# curtain.net
KiCad netlist of a schematic drawn in EAGLE
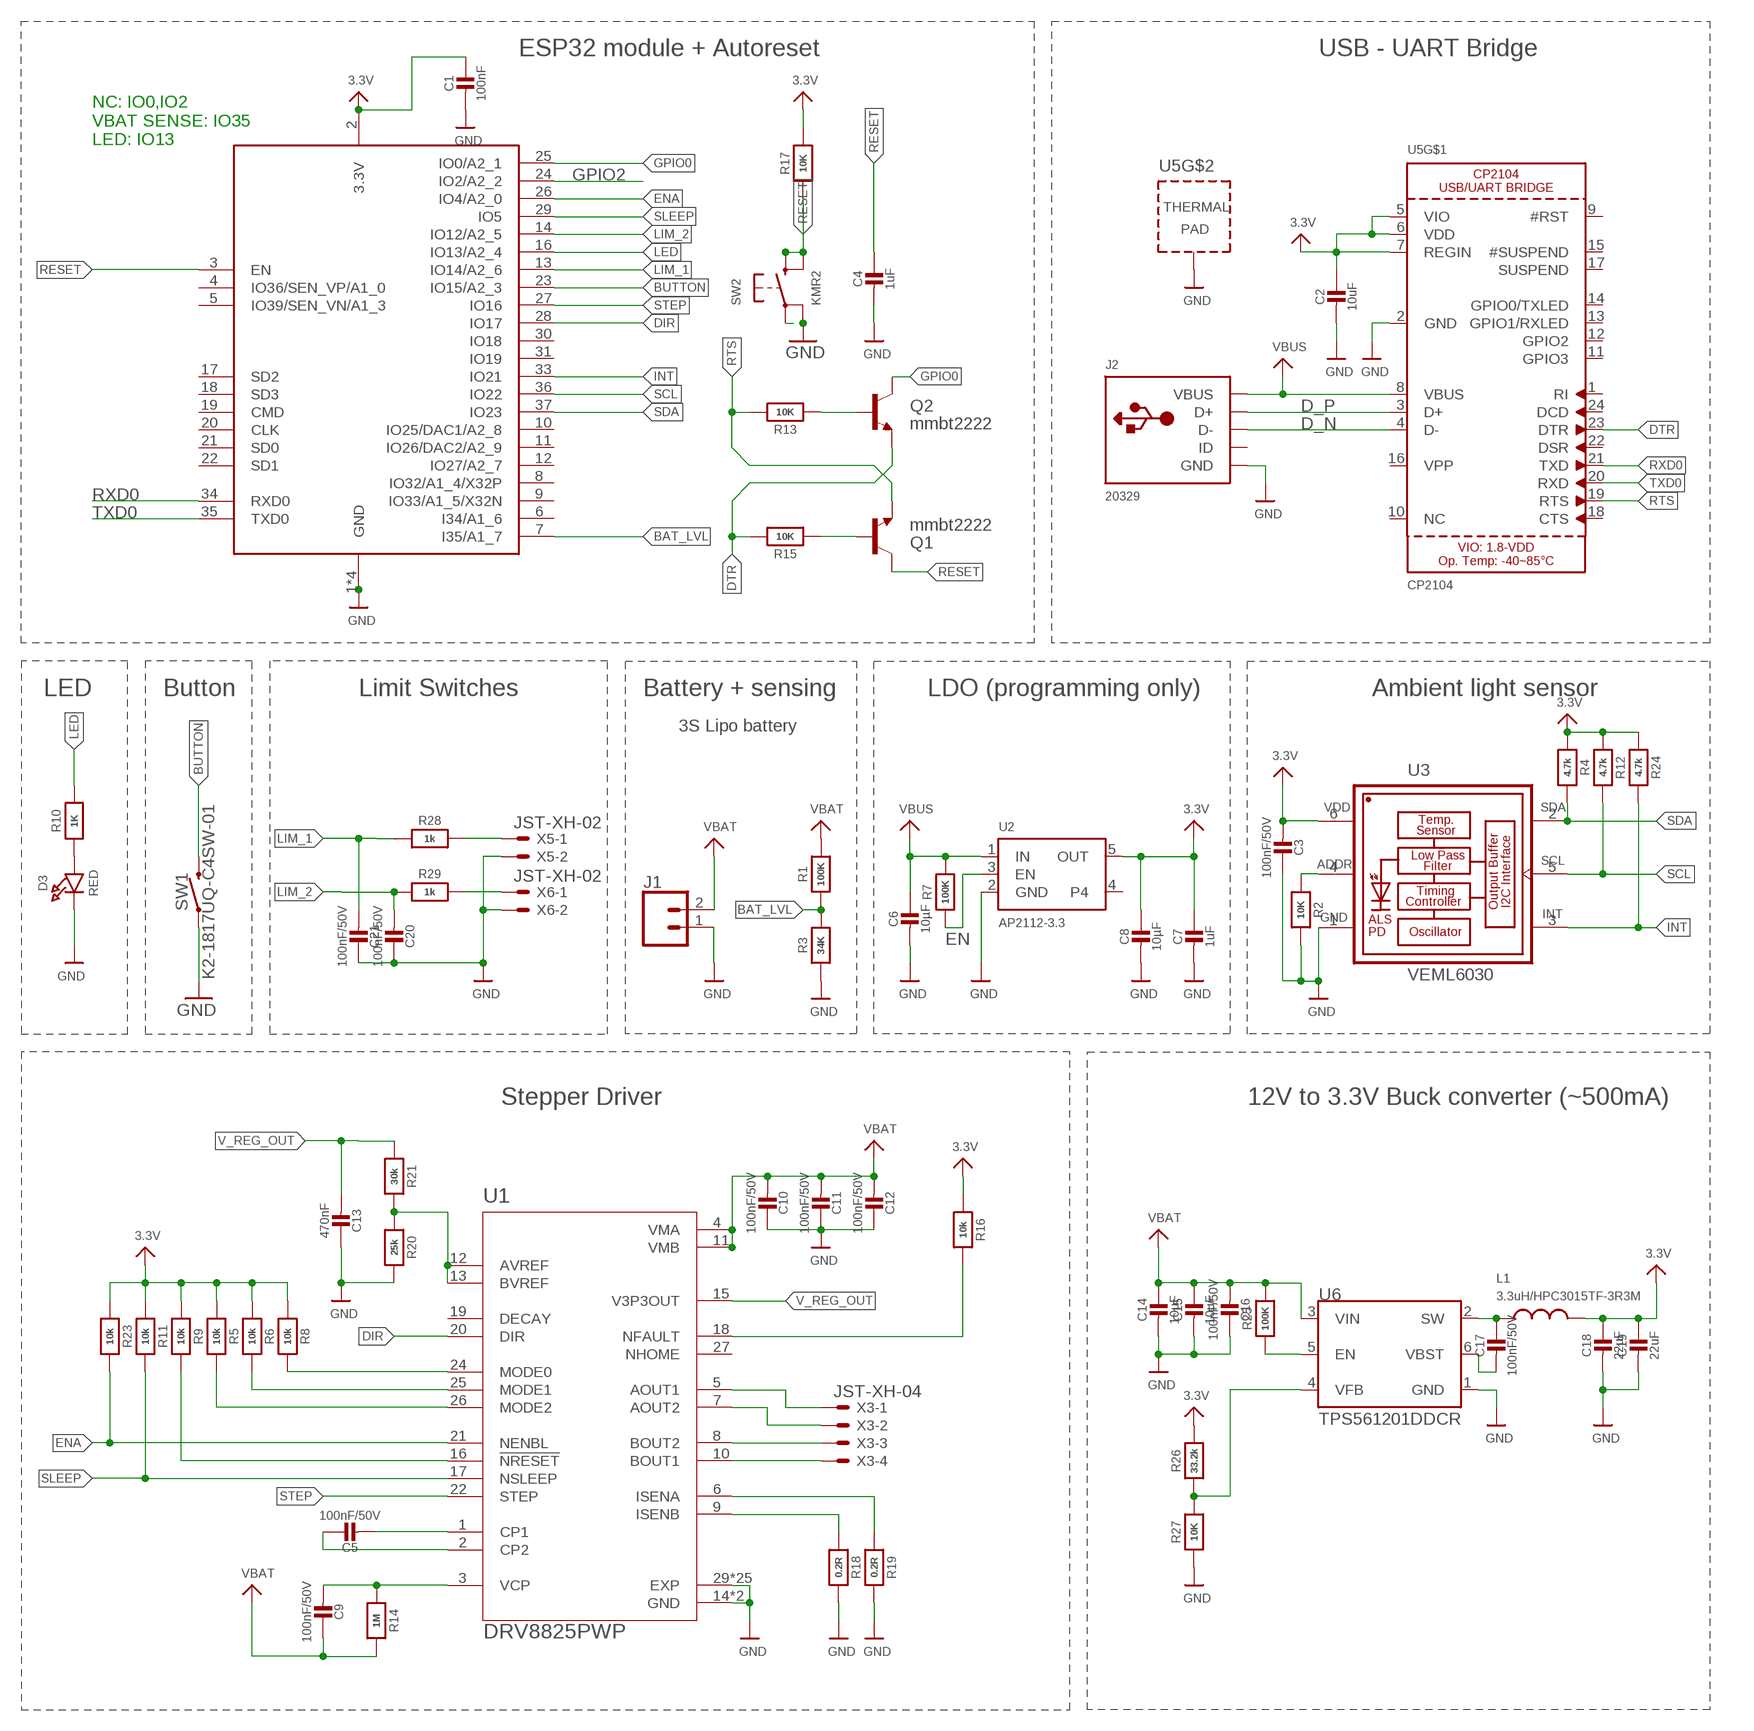
[diagram p0: schematic, sheet 1]

(export (version "E")
  (design (tool "Eeschema 10.0.6"))
  (components
    (comp (ref "C1")
      (value "100nF")
      (footprint "eagle-import:_0402")
      (libsource (lib "eagle-import") (part "CAP_CERAMIC_0402"))
    )
    (comp (ref "C2")
      (value "10uF")
      (footprint "eagle-import:_0402")
      (libsource (lib "eagle-import") (part "CAP_CERAMIC_0402"))
    )
    (comp (ref "C3")
      (value "100nF/50V")
      (footprint "eagle-import:_0402")
      (libsource (lib "eagle-import") (part "CAP_CERAMIC_0402"))
    )
    (comp (ref "C4")
      (value "1uF")
      (footprint "eagle-import:_0402")
      (libsource (lib "eagle-import") (part "CAP_CERAMIC_0402"))
    )
    (comp (ref "C5")
      (value "100nF/50V")
      (footprint "eagle-import:_0805")
      (libsource (lib "eagle-import") (part "CAP_CERAMIC_0805"))
    )
    (comp (ref "C6")
      (value "10µF")
      (footprint "eagle-import:_0402")
      (libsource (lib "eagle-import") (part "CAP_CERAMIC_0402"))
    )
    (comp (ref "C7")
      (value "1uF")
      (footprint "eagle-import:_0402")
      (libsource (lib "eagle-import") (part "CAP_CERAMIC_0402"))
    )
    (comp (ref "C8")
      (value "10µF")
      (footprint "eagle-import:_0402")
      (libsource (lib "eagle-import") (part "CAP_CERAMIC_0402"))
    )
    (comp (ref "C9")
      (value "100nF/50V")
      (footprint "eagle-import:_0805")
      (libsource (lib "eagle-import") (part "CAP_CERAMIC_0805"))
    )
    (comp (ref "C10")
      (value "100nF/50V")
      (footprint "eagle-import:_0805")
      (libsource (lib "eagle-import") (part "CAP_CERAMIC_0805"))
    )
    (comp (ref "C11")
      (value "100nF/50V")
      (footprint "eagle-import:_0805")
      (libsource (lib "eagle-import") (part "CAP_CERAMIC_0805"))
    )
    (comp (ref "C12")
      (value "100nF/50V")
      (footprint "eagle-import:_0805")
      (libsource (lib "eagle-import") (part "CAP_CERAMIC_0805"))
    )
    (comp (ref "C13")
      (value "470nF")
      (footprint "eagle-import:_0402")
      (libsource (lib "eagle-import") (part "CAP_CERAMIC_0402"))
    )
    (comp (ref "C14")
      (value "10µF")
      (footprint "eagle-import:_0402")
      (libsource (lib "eagle-import") (part "CAP_CERAMIC_0402"))
    )
    (comp (ref "C15")
      (value "10µF")
      (footprint "eagle-import:_0402")
      (libsource (lib "eagle-import") (part "CAP_CERAMIC_0402"))
    )
    (comp (ref "C16")
      (value "100nF/50V")
      (footprint "eagle-import:_0402")
      (libsource (lib "eagle-import") (part "CAP_CERAMIC_0402"))
    )
    (comp (ref "C17")
      (value "100nF/50V")
      (footprint "eagle-import:_0402")
      (libsource (lib "eagle-import") (part "CAP_CERAMIC_0402"))
    )
    (comp (ref "C18")
      (value "22uF")
      (footprint "eagle-import:_0402")
      (libsource (lib "eagle-import") (part "CAP_CERAMIC_0402"))
    )
    (comp (ref "C19")
      (value "22uF")
      (footprint "eagle-import:_0402")
      (libsource (lib "eagle-import") (part "CAP_CERAMIC_0402"))
    )
    (comp (ref "C20")
      (value "100nF/50V")
      (footprint "eagle-import:_0402")
      (libsource (lib "eagle-import") (part "CAP_CERAMIC_0402"))
    )
    (comp (ref "C21")
      (value "100nF/50V")
      (footprint "eagle-import:_0402")
      (libsource (lib "eagle-import") (part "CAP_CERAMIC_0402"))
    )
    (comp (ref "D3")
      (value "RED")
      (footprint "eagle-import:CHIPLED_0805_NOOUTLINE")
      (libsource (lib "eagle-import") (part "LED0805_NOOUTLINE"))
    )
    (comp (ref "J1")
      (value "CONN_023.5MM_LOCK")
      (footprint "eagle-import:SCREWTERMINAL-3.5MM-2_LOCK")
      (libsource (lib "eagle-import") (part "CONN_023.5MM_LOCK"))
    )
    (comp (ref "J2")
      (value "20329")
      (footprint "eagle-import:4UCONN_20329_V2")
      (libsource (lib "eagle-import") (part "USB_MICRO_20329_V2"))
    )
    (comp (ref "L1")
      (value "3.3uH/HPC3015TF-3R3M")
      (footprint "eagle-import:WPN4020H100MT")
      (libsource (lib "eagle-import") (part "WPN4020H100MT"))
    )
    (comp (ref "Q1")
      (value "mmbt2222")
      (footprint "eagle-import:SOT23-3")
      (libsource (lib "eagle-import") (part "TRANSISTOR_NPNSOT23-3"))
    )
    (comp (ref "Q2")
      (value "mmbt2222")
      (footprint "eagle-import:SOT23-3")
      (libsource (lib "eagle-import") (part "TRANSISTOR_NPNSOT23-3"))
    )
    (comp (ref "R1")
      (value "100K")
      (footprint "eagle-import:_0402")
      (libsource (lib "eagle-import") (part "RESISTOR_0402"))
    )
    (comp (ref "R2")
      (value "10K")
      (footprint "eagle-import:_0402")
      (libsource (lib "eagle-import") (part "RESISTOR_0402"))
    )
    (comp (ref "R3")
      (value "34K")
      (footprint "eagle-import:_0402")
      (libsource (lib "eagle-import") (part "RESISTOR_0402"))
    )
    (comp (ref "R4")
      (value "4.7k")
      (footprint "eagle-import:_0402")
      (libsource (lib "eagle-import") (part "RESISTOR_0402"))
    )
    (comp (ref "R5")
      (value "10k")
      (footprint "eagle-import:_0402")
      (libsource (lib "eagle-import") (part "RESISTOR_0402"))
    )
    (comp (ref "R6")
      (value "10k")
      (footprint "eagle-import:_0402")
      (libsource (lib "eagle-import") (part "RESISTOR_0402"))
    )
    (comp (ref "R7")
      (value "100K")
      (footprint "eagle-import:_0402")
      (libsource (lib "eagle-import") (part "RESISTOR_0402"))
    )
    (comp (ref "R8")
      (value "10k")
      (footprint "eagle-import:_0402")
      (libsource (lib "eagle-import") (part "RESISTOR_0402"))
    )
    (comp (ref "R9")
      (value "10k")
      (footprint "eagle-import:_0402")
      (libsource (lib "eagle-import") (part "RESISTOR_0402"))
    )
    (comp (ref "R10")
      (value "1K")
      (footprint "eagle-import:_0402")
      (libsource (lib "eagle-import") (part "RESISTOR_0402"))
    )
    (comp (ref "R11")
      (value "10k")
      (footprint "eagle-import:_0402")
      (libsource (lib "eagle-import") (part "RESISTOR_0402"))
    )
    (comp (ref "R12")
      (value "4.7k")
      (footprint "eagle-import:_0402")
      (libsource (lib "eagle-import") (part "RESISTOR_0402"))
    )
    (comp (ref "R13")
      (value "10K")
      (footprint "eagle-import:_0402")
      (libsource (lib "eagle-import") (part "RESISTOR_0402"))
    )
    (comp (ref "R14")
      (value "1M")
      (footprint "eagle-import:_0402")
      (libsource (lib "eagle-import") (part "RESISTOR_0402"))
    )
    (comp (ref "R15")
      (value "10K")
      (footprint "eagle-import:_0402")
      (libsource (lib "eagle-import") (part "RESISTOR_0402"))
    )
    (comp (ref "R16")
      (value "10k")
      (footprint "eagle-import:_0402")
      (libsource (lib "eagle-import") (part "RESISTOR_0402"))
    )
    (comp (ref "R17")
      (value "10K")
      (footprint "eagle-import:_0402")
      (libsource (lib "eagle-import") (part "RESISTOR_0402"))
    )
    (comp (ref "R18")
      (value "0.2R")
      (footprint "eagle-import:_1206")
      (libsource (lib "eagle-import") (part "RESISTOR_1206"))
    )
    (comp (ref "R19")
      (value "0.2R")
      (footprint "eagle-import:_1206")
      (libsource (lib "eagle-import") (part "RESISTOR_1206"))
    )
    (comp (ref "R20")
      (value "25k")
      (footprint "eagle-import:_0402")
      (libsource (lib "eagle-import") (part "RESISTOR_0402"))
    )
    (comp (ref "R21")
      (value "30k")
      (footprint "eagle-import:_0402")
      (libsource (lib "eagle-import") (part "RESISTOR_0402"))
    )
    (comp (ref "R23")
      (value "10k")
      (footprint "eagle-import:_0402")
      (libsource (lib "eagle-import") (part "RESISTOR_0402"))
    )
    (comp (ref "R24")
      (value "4.7k")
      (footprint "eagle-import:_0402")
      (libsource (lib "eagle-import") (part "RESISTOR_0402"))
    )
    (comp (ref "R25")
      (value "100K")
      (footprint "eagle-import:_0402")
      (libsource (lib "eagle-import") (part "RESISTOR_0402"))
    )
    (comp (ref "R26")
      (value "33.2k")
      (footprint "eagle-import:_0402")
      (libsource (lib "eagle-import") (part "RESISTOR_0402"))
    )
    (comp (ref "R27")
      (value "10K")
      (footprint "eagle-import:_0402")
      (libsource (lib "eagle-import") (part "RESISTOR_0402"))
    )
    (comp (ref "R28")
      (value "1k")
      (footprint "eagle-import:_0402")
      (libsource (lib "eagle-import") (part "RESISTOR_0402"))
    )
    (comp (ref "R29")
      (value "1k")
      (footprint "eagle-import:_0402")
      (libsource (lib "eagle-import") (part "RESISTOR_0402"))
    )
    (comp (ref "SW1")
      (value "K2-1817UQ-C4SW-01")
      (footprint "eagle-import:K2-1817UQ-C4SW-01")
      (libsource (lib "eagle-import") (part "K2-1817UQ-C4SW-01"))
    )
    (comp (ref "SW2")
      (value "KMR2")
      (footprint "eagle-import:BTN_KMR2_4.6X2.8")
      (libsource (lib "eagle-import") (part "SWITCH_TACT_SMT4.6X2.8"))
    )
    (comp (ref "U1")
      (value "DRV8825PWP")
      (footprint "eagle-import:SOP65P640X120-29N")
      (fields (field (name "MF") "Texas Instruments"))
      (libsource (lib "eagle-import") (part "DRV8825PWP"))
    )
    (comp (ref "U2")
      (value "AP2112-3.3")
      (footprint "eagle-import:SOT23-5")
      (libsource (lib "eagle-import") (part "VREG_SOT23-5"))
    )
    (comp (ref "U3")
      (value "VEML6030")
      (footprint "eagle-import:VISHAY_VEML6030_2X2X0.87")
      (fields (field (name "MF") "Vishay"))
      (libsource (lib "eagle-import") (part "VEML6030"))
    )
    (comp (ref "U4")
      (value "ESP32_WROOM32_SKINNY")
      (footprint "eagle-import:WROOM32_SKINNY")
      (libsource (lib "eagle-import") (part "ESP32_WROOM32_SKINNY"))
    )
    (comp (ref "U5")
      (value "CP2104")
      (footprint "eagle-import:QFN24_4MM_SMSC")
      (libsource (lib "eagle-import") (part "CP2104"))
    )
    (comp (ref "U6")
      (value "TPS561201DDCR")
      (footprint "eagle-import:SOT95P280X110-6N")
      (fields (field (name "MF") "Texas Instruments"))
      (libsource (lib "eagle-import") (part "TPS561201DDCR"))
    )
    (comp (ref "X3")
      (value "JST-XH-04")
      (footprint "eagle-import:JST-XH-04-PACKAGE-ROUND-PAD")
      (libsource (lib "eagle-import") (part "JST-XH-04-PIN-ROUND-PAD"))
    )
    (comp (ref "X5")
      (value "JST-XH-02")
      (footprint "eagle-import:JST-XH-02-PACKAGE-ROUND-PAD")
      (libsource (lib "eagle-import") (part "JST-XH-02-PIN-ROUND-PAD"))
    )
    (comp (ref "X6")
      (value "JST-XH-02")
      (footprint "eagle-import:JST-XH-02-PACKAGE-ROUND-PAD")
      (libsource (lib "eagle-import") (part "JST-XH-02-PIN-ROUND-PAD"))
    )
  )
  (nets
    (net (code "1") (name "/D_N") (class "Default")
      (node (ref "J2") (pin "D-") (pinfunction "D-_D-") (pintype "bidirectional"))
      (node (ref "U5") (pin "4") (pinfunction "D-_4") (pintype "bidirectional"))
    )
    (net (code "2") (name "/D_P") (class "Default")
      (node (ref "J2") (pin "D+") (pinfunction "D+_D+") (pintype "bidirectional"))
      (node (ref "U5") (pin "3") (pinfunction "D+_3") (pintype "bidirectional"))
    )
    (net (code "3") (name "/EN") (class "Default")
      (node (ref "R7") (pin "1") (pinfunction "1_1") (pintype "passive"))
      (node (ref "U2") (pin "3") (pinfunction "EN_3") (pintype "input"))
    )
    (net (code "4") (name "/GPIO2") (class "Default")
      (node (ref "U4") (pin "24") (pinfunction "IO2/A2_2_24") (pintype "bidirectional"))
    )
    (net (code "5") (name "3.3V") (class "Default")
      (node (ref "C1") (pin "1") (pinfunction "1_1") (pintype "passive"))
      (node (ref "C18") (pin "1") (pinfunction "1_1") (pintype "passive"))
      (node (ref "C19") (pin "1") (pinfunction "1_1") (pintype "passive"))
      (node (ref "C2") (pin "1") (pinfunction "1_1") (pintype "passive"))
      (node (ref "C3") (pin "2") (pinfunction "2_2") (pintype "passive"))
      (node (ref "C7") (pin "1") (pinfunction "1_1") (pintype "passive"))
      (node (ref "C8") (pin "1") (pinfunction "1_1") (pintype "passive"))
      (node (ref "L1") (pin "2") (pinfunction "2_2") (pintype "passive"))
      (node (ref "R11") (pin "1") (pinfunction "1_1") (pintype "passive"))
      (node (ref "R12") (pin "1") (pinfunction "1_1") (pintype "passive"))
      (node (ref "R16") (pin "1") (pinfunction "1_1") (pintype "passive"))
      (node (ref "R17") (pin "2") (pinfunction "2_2") (pintype "passive"))
      (node (ref "R23") (pin "1") (pinfunction "1_1") (pintype "passive"))
      (node (ref "R24") (pin "1") (pinfunction "1_1") (pintype "passive"))
      (node (ref "R26") (pin "1") (pinfunction "1_1") (pintype "passive"))
      (node (ref "R4") (pin "1") (pinfunction "1_1") (pintype "passive"))
      (node (ref "R5") (pin "1") (pinfunction "1_1") (pintype "passive"))
      (node (ref "R6") (pin "1") (pinfunction "1_1") (pintype "passive"))
      (node (ref "R8") (pin "1") (pinfunction "1_1") (pintype "passive"))
      (node (ref "R9") (pin "1") (pinfunction "1_1") (pintype "passive"))
      (node (ref "U2") (pin "5") (pinfunction "OUT_5") (pintype "power_in"))
      (node (ref "U3") (pin "6") (pinfunction "VDD_6") (pintype "power_in"))
      (node (ref "U4") (pin "2") (pinfunction "3.3V_2") (pintype "passive"))
      (node (ref "U5") (pin "5") (pinfunction "VIO_5") (pintype "power_in"))
      (node (ref "U5") (pin "6") (pinfunction "VDD_6") (pintype "power_in"))
      (node (ref "U5") (pin "7") (pinfunction "REGIN_7") (pintype "power_in"))
    )
    (net (code "6") (name "BAT_LVL") (class "Default")
      (node (ref "R1") (pin "1") (pinfunction "1_1") (pintype "passive"))
      (node (ref "R3") (pin "2") (pinfunction "2_2") (pintype "passive"))
      (node (ref "U4") (pin "7") (pinfunction "I35/A1_7_7") (pintype "bidirectional"))
    )
    (net (code "7") (name "BUTTON") (class "Default")
      (node (ref "SW1") (pin "P$2") (pinfunction "2_P$2") (pintype "passive"))
      (node (ref "U4") (pin "23") (pinfunction "IO15/A2_3_23") (pintype "bidirectional"))
    )
    (net (code "8") (name "DIR") (class "Default")
      (node (ref "U1") (pin "20") (pinfunction "DIR_20") (pintype "input"))
      (node (ref "U4") (pin "28") (pinfunction "IO17_28") (pintype "bidirectional"))
    )
    (net (code "9") (name "DTR") (class "Default")
      (node (ref "Q2") (pin "2") (pinfunction "E_2") (pintype "passive"))
      (node (ref "R15") (pin "2") (pinfunction "2_2") (pintype "passive"))
      (node (ref "U5") (pin "23") (pinfunction "DTR_23") (pintype "output"))
    )
    (net (code "10") (name "ENA") (class "Default")
      (node (ref "R23") (pin "2") (pinfunction "2_2") (pintype "passive"))
      (node (ref "U1") (pin "21") (pinfunction "NENBL_21") (pintype "input"))
      (node (ref "U4") (pin "26") (pinfunction "IO4/A2_0_26") (pintype "bidirectional"))
    )
    (net (code "11") (name "GND") (class "Default")
      (node (ref "C1") (pin "2") (pinfunction "2_2") (pintype "passive"))
      (node (ref "C10") (pin "1") (pinfunction "1_1") (pintype "passive"))
      (node (ref "C11") (pin "1") (pinfunction "1_1") (pintype "passive"))
      (node (ref "C12") (pin "1") (pinfunction "1_1") (pintype "passive"))
      (node (ref "C13") (pin "1") (pinfunction "1_1") (pintype "passive"))
      (node (ref "C14") (pin "2") (pinfunction "2_2") (pintype "passive"))
      (node (ref "C15") (pin "2") (pinfunction "2_2") (pintype "passive"))
      (node (ref "C16") (pin "1") (pinfunction "1_1") (pintype "passive"))
      (node (ref "C18") (pin "2") (pinfunction "2_2") (pintype "passive"))
      (node (ref "C19") (pin "2") (pinfunction "2_2") (pintype "passive"))
      (node (ref "C2") (pin "2") (pinfunction "2_2") (pintype "passive"))
      (node (ref "C20") (pin "1") (pinfunction "1_1") (pintype "passive"))
      (node (ref "C21") (pin "1") (pinfunction "1_1") (pintype "passive"))
      (node (ref "C3") (pin "1") (pinfunction "1_1") (pintype "passive"))
      (node (ref "C4") (pin "2") (pinfunction "2_2") (pintype "passive"))
      (node (ref "C6") (pin "2") (pinfunction "2_2") (pintype "passive"))
      (node (ref "C7") (pin "2") (pinfunction "2_2") (pintype "passive"))
      (node (ref "C8") (pin "2") (pinfunction "2_2") (pintype "passive"))
      (node (ref "D3") (pin "C") (pinfunction "C_C") (pintype "passive"))
      (node (ref "J1") (pin "1") (pinfunction "1_1") (pintype "passive"))
      (node (ref "J2") (pin "BASE@1") (pinfunction "GND_BASE@1") (pintype "power_in"))
      (node (ref "J2") (pin "BASE@2") (pinfunction "GND_BASE@2") (pintype "power_in"))
      (node (ref "J2") (pin "GND") (pinfunction "GND_GND") (pintype "power_in"))
      (node (ref "J2") (pin "SPRT@1") (pinfunction "GND_SPRT@1") (pintype "power_in"))
      (node (ref "J2") (pin "SPRT@2") (pinfunction "GND_SPRT@2") (pintype "power_in"))
      (node (ref "J2") (pin "SPRT@3") (pinfunction "GND_SPRT@3") (pintype "power_in"))
      (node (ref "J2") (pin "SPRT@4") (pinfunction "GND_SPRT@4") (pintype "power_in"))
      (node (ref "R18") (pin "2") (pinfunction "2_2") (pintype "passive"))
      (node (ref "R19") (pin "2") (pinfunction "2_2") (pintype "passive"))
      (node (ref "R2") (pin "2") (pinfunction "2_2") (pintype "passive"))
      (node (ref "R20") (pin "2") (pinfunction "2_2") (pintype "passive"))
      (node (ref "R27") (pin "1") (pinfunction "1_1") (pintype "passive"))
      (node (ref "R3") (pin "1") (pinfunction "1_1") (pintype "passive"))
      (node (ref "SW1") (pin "P$1") (pinfunction "1_P$1") (pintype "passive"))
      (node (ref "SW2") (pin "A'") (pinfunction "P1_A'") (pintype "passive"))
      (node (ref "U1") (pin "14") (pinfunction "GND_14") (pintype "power_in"))
      (node (ref "U1") (pin "28") (pinfunction "GND_28") (pintype "power_in"))
      (node (ref "U1") (pin "29") (pinfunction "EXP_29") (pintype "power_in"))
      (node (ref "U1") (pin "P1") (pinfunction "EXP_P1") (pintype "power_in"))
      (node (ref "U1") (pin "P10") (pinfunction "EXP_P10") (pintype "power_in"))
      (node (ref "U1") (pin "P11") (pinfunction "EXP_P11") (pintype "power_in"))
      (node (ref "U1") (pin "P12") (pinfunction "EXP_P12") (pintype "power_in"))
      (node (ref "U1") (pin "P13") (pinfunction "EXP_P13") (pintype "power_in"))
      (node (ref "U1") (pin "P14") (pinfunction "EXP_P14") (pintype "power_in"))
      (node (ref "U1") (pin "P15") (pinfunction "EXP_P15") (pintype "power_in"))
      (node (ref "U1") (pin "P16") (pinfunction "EXP_P16") (pintype "power_in"))
      (node (ref "U1") (pin "P17") (pinfunction "EXP_P17") (pintype "power_in"))
      (node (ref "U1") (pin "P18") (pinfunction "EXP_P18") (pintype "power_in"))
      (node (ref "U1") (pin "P19") (pinfunction "EXP_P19") (pintype "power_in"))
      (node (ref "U1") (pin "P2") (pinfunction "EXP_P2") (pintype "power_in"))
      (node (ref "U1") (pin "P20") (pinfunction "EXP_P20") (pintype "power_in"))
      (node (ref "U1") (pin "P21") (pinfunction "EXP_P21") (pintype "power_in"))
      (node (ref "U1") (pin "P22") (pinfunction "EXP_P22") (pintype "power_in"))
      (node (ref "U1") (pin "P23") (pinfunction "EXP_P23") (pintype "power_in"))
      (node (ref "U1") (pin "P24") (pinfunction "EXP_P24") (pintype "power_in"))
      (node (ref "U1") (pin "P3") (pinfunction "EXP_P3") (pintype "power_in"))
      (node (ref "U1") (pin "P4") (pinfunction "EXP_P4") (pintype "power_in"))
      (node (ref "U1") (pin "P5") (pinfunction "EXP_P5") (pintype "power_in"))
      (node (ref "U1") (pin "P6") (pinfunction "EXP_P6") (pintype "power_in"))
      (node (ref "U1") (pin "P7") (pinfunction "EXP_P7") (pintype "power_in"))
      (node (ref "U1") (pin "P8") (pinfunction "EXP_P8") (pintype "power_in"))
      (node (ref "U1") (pin "P9") (pinfunction "EXP_P9") (pintype "power_in"))
      (node (ref "U2") (pin "2") (pinfunction "GND_2") (pintype "power_in"))
      (node (ref "U3") (pin "1") (pinfunction "GND_1") (pintype "power_in"))
      (node (ref "U4") (pin "1") (pinfunction "GND_1") (pintype "passive"))
      (node (ref "U4") (pin "15") (pinfunction "GND_15") (pintype "passive"))
      (node (ref "U4") (pin "38") (pinfunction "GND_38") (pintype "passive"))
      (node (ref "U4") (pin "P$1") (pinfunction "GND_P$1") (pintype "passive"))
      (node (ref "U5") (pin "2") (pinfunction "GND_2") (pintype "power_in"))
      (node (ref "U5") (pin "THERM") (pinfunction "TP_THERM") (pintype "power_in"))
      (node (ref "U6") (pin "1") (pinfunction "GND_1") (pintype "power_in"))
      (node (ref "X5") (pin "2") (pinfunction "S_2") (pintype "passive"))
      (node (ref "X6") (pin "2") (pinfunction "S_2") (pintype "passive"))
    )
    (net (code "12") (name "GPIO0") (class "Default")
      (node (ref "Q2") (pin "3") (pinfunction "C_3") (pintype "passive"))
      (node (ref "U4") (pin "25") (pinfunction "IO0/A2_1_25") (pintype "bidirectional"))
    )
    (net (code "13") (name "INT") (class "Default")
      (node (ref "R24") (pin "2") (pinfunction "2_2") (pintype "passive"))
      (node (ref "U3") (pin "3") (pinfunction "INT_3") (pintype "output"))
      (node (ref "U4") (pin "33") (pinfunction "IO21_33") (pintype "bidirectional"))
    )
    (net (code "14") (name "LED") (class "Default")
      (node (ref "R10") (pin "1") (pinfunction "1_1") (pintype "passive"))
      (node (ref "U4") (pin "16") (pinfunction "IO13/A2_4_16") (pintype "bidirectional"))
    )
    (net (code "15") (name "LIM_1") (class "Default")
      (node (ref "C21") (pin "2") (pinfunction "2_2") (pintype "passive"))
      (node (ref "R28") (pin "1") (pinfunction "1_1") (pintype "passive"))
      (node (ref "U4") (pin "13") (pinfunction "IO14/A2_6_13") (pintype "bidirectional"))
    )
    (net (code "16") (name "LIM_2") (class "Default")
      (node (ref "C20") (pin "2") (pinfunction "2_2") (pintype "passive"))
      (node (ref "R29") (pin "1") (pinfunction "1_1") (pintype "passive"))
      (node (ref "U4") (pin "14") (pinfunction "IO12/A2_5_14") (pintype "bidirectional"))
    )
    (net (code "17") (name "Net-(D3-PadA)") (class "Default")
      (node (ref "D3") (pin "A") (pinfunction "A_A") (pintype "passive"))
      (node (ref "R10") (pin "2") (pinfunction "2_2") (pintype "passive"))
    )
    (net (code "18") (name "Net-(Q1-B)") (class "Default")
      (node (ref "Q1") (pin "1") (pinfunction "B_1") (pintype "passive"))
      (node (ref "R15") (pin "1") (pinfunction "1_1") (pintype "passive"))
    )
    (net (code "19") (name "Net-(Q2-B)") (class "Default")
      (node (ref "Q2") (pin "1") (pinfunction "B_1") (pintype "passive"))
      (node (ref "R13") (pin "1") (pinfunction "1_1") (pintype "passive"))
    )
    (net (code "20") (name "Net-(U1-AOUT1)") (class "Default")
      (node (ref "U1") (pin "5") (pinfunction "AOUT1_5") (pintype "output"))
      (node (ref "X3") (pin "1") (pinfunction "S_1") (pintype "passive"))
    )
    (net (code "21") (name "Net-(U1-AOUT2)") (class "Default")
      (node (ref "U1") (pin "7") (pinfunction "AOUT2_7") (pintype "output"))
      (node (ref "X3") (pin "2") (pinfunction "S_2") (pintype "passive"))
    )
    (net (code "22") (name "Net-(U1-AVREF)") (class "Default")
      (node (ref "R20") (pin "1") (pinfunction "1_1") (pintype "passive"))
      (node (ref "R21") (pin "2") (pinfunction "2_2") (pintype "passive"))
      (node (ref "U1") (pin "12") (pinfunction "AVREF_12") (pintype "input"))
      (node (ref "U1") (pin "13") (pinfunction "BVREF_13") (pintype "input"))
    )
    (net (code "23") (name "Net-(U1-BOUT1)") (class "Default")
      (node (ref "U1") (pin "10") (pinfunction "BOUT1_10") (pintype "output"))
      (node (ref "X3") (pin "4") (pinfunction "S_4") (pintype "passive"))
    )
    (net (code "24") (name "Net-(U1-BOUT2)") (class "Default")
      (node (ref "U1") (pin "8") (pinfunction "BOUT2_8") (pintype "output"))
      (node (ref "X3") (pin "3") (pinfunction "S_3") (pintype "passive"))
    )
    (net (code "25") (name "Net-(U1-CP1)") (class "Default")
      (node (ref "C5") (pin "2") (pinfunction "2_2") (pintype "passive"))
      (node (ref "U1") (pin "1") (pinfunction "CP1_1") (pintype "bidirectional"))
    )
    (net (code "26") (name "Net-(U1-CP2)") (class "Default")
      (node (ref "C5") (pin "1") (pinfunction "1_1") (pintype "passive"))
      (node (ref "U1") (pin "2") (pinfunction "CP2_2") (pintype "bidirectional"))
    )
    (net (code "27") (name "Net-(U1-ISENA)") (class "Default")
      (node (ref "R19") (pin "1") (pinfunction "1_1") (pintype "passive"))
      (node (ref "U1") (pin "6") (pinfunction "ISENA_6") (pintype "bidirectional"))
    )
    (net (code "28") (name "Net-(U1-ISENB)") (class "Default")
      (node (ref "R18") (pin "1") (pinfunction "1_1") (pintype "passive"))
      (node (ref "U1") (pin "9") (pinfunction "ISENB_9") (pintype "bidirectional"))
    )
    (net (code "29") (name "Net-(U1-MODE0)") (class "Default")
      (node (ref "R8") (pin "2") (pinfunction "2_2") (pintype "passive"))
      (node (ref "U1") (pin "24") (pinfunction "MODE0_24") (pintype "input"))
    )
    (net (code "30") (name "Net-(U1-MODE1)") (class "Default")
      (node (ref "R6") (pin "2") (pinfunction "2_2") (pintype "passive"))
      (node (ref "U1") (pin "25") (pinfunction "MODE1_25") (pintype "input"))
    )
    (net (code "31") (name "Net-(U1-MODE2)") (class "Default")
      (node (ref "R5") (pin "2") (pinfunction "2_2") (pintype "passive"))
      (node (ref "U1") (pin "26") (pinfunction "MODE2_26") (pintype "input"))
    )
    (net (code "32") (name "Net-(U1-NFAULT)") (class "Default")
      (node (ref "R16") (pin "2") (pinfunction "2_2") (pintype "passive"))
      (node (ref "U1") (pin "18") (pinfunction "NFAULT_18") (pintype "output"))
    )
    (net (code "33") (name "Net-(U1-VCP)") (class "Default")
      (node (ref "C9") (pin "2") (pinfunction "2_2") (pintype "passive"))
      (node (ref "R14") (pin "1") (pinfunction "1_1") (pintype "passive"))
      (node (ref "U1") (pin "3") (pinfunction "VCP_3") (pintype "bidirectional"))
    )
    (net (code "34") (name "Net-(U1-~{NRESET})") (class "Default")
      (node (ref "R9") (pin "2") (pinfunction "2_2") (pintype "passive"))
      (node (ref "U1") (pin "16") (pinfunction "~{NRESET}_16") (pintype "input"))
    )
    (net (code "35") (name "Net-(U3-ADDR)") (class "Default")
      (node (ref "R2") (pin "1") (pinfunction "1_1") (pintype "passive"))
      (node (ref "U3") (pin "4") (pinfunction "ADDR_4") (pintype "bidirectional"))
    )
    (net (code "36") (name "Net-(U6-EN)") (class "Default")
      (node (ref "R25") (pin "1") (pinfunction "1_1") (pintype "passive"))
      (node (ref "U6") (pin "5") (pinfunction "EN_5") (pintype "input"))
    )
    (net (code "37") (name "Net-(U6-SW)") (class "Default")
      (node (ref "C17") (pin "1") (pinfunction "1_1") (pintype "passive"))
      (node (ref "L1") (pin "1") (pinfunction "1_1") (pintype "passive"))
      (node (ref "U6") (pin "2") (pinfunction "SW_2") (pintype "output"))
    )
    (net (code "38") (name "Net-(U6-VBST)") (class "Default")
      (node (ref "C17") (pin "2") (pinfunction "2_2") (pintype "passive"))
      (node (ref "U6") (pin "6") (pinfunction "VBST_6") (pintype "passive"))
    )
    (net (code "39") (name "Net-(U6-VFB)") (class "Default")
      (node (ref "R26") (pin "2") (pinfunction "2_2") (pintype "passive"))
      (node (ref "R27") (pin "2") (pinfunction "2_2") (pintype "passive"))
      (node (ref "U6") (pin "4") (pinfunction "VFB_4") (pintype "input"))
    )
    (net (code "40") (name "Net-(X5A-S)") (class "Default")
      (node (ref "R28") (pin "2") (pinfunction "2_2") (pintype "passive"))
      (node (ref "X5") (pin "1") (pinfunction "S_1") (pintype "passive"))
    )
    (net (code "41") (name "Net-(X6A-S)") (class "Default")
      (node (ref "R29") (pin "2") (pinfunction "2_2") (pintype "passive"))
      (node (ref "X6") (pin "1") (pinfunction "S_1") (pintype "passive"))
    )
    (net (code "42") (name "RESET") (class "Default")
      (node (ref "C4") (pin "1") (pinfunction "1_1") (pintype "passive"))
      (node (ref "Q1") (pin "3") (pinfunction "C_3") (pintype "passive"))
      (node (ref "R17") (pin "1") (pinfunction "1_1") (pintype "passive"))
      (node (ref "SW2") (pin "B") (pinfunction "S_B") (pintype "passive"))
      (node (ref "SW2") (pin "B'") (pinfunction "S1_B'") (pintype "passive"))
      (node (ref "U4") (pin "3") (pinfunction "EN_3") (pintype "input"))
    )
    (net (code "43") (name "RTS") (class "Default")
      (node (ref "Q1") (pin "2") (pinfunction "E_2") (pintype "passive"))
      (node (ref "R13") (pin "2") (pinfunction "2_2") (pintype "passive"))
      (node (ref "U5") (pin "19") (pinfunction "RTS_19") (pintype "output"))
    )
    (net (code "44") (name "RXD0") (class "Default")
      (node (ref "U4") (pin "34") (pinfunction "RXD0_34") (pintype "input"))
      (node (ref "U5") (pin "21") (pinfunction "TXD_21") (pintype "output"))
    )
    (net (code "45") (name "SCL") (class "Default")
      (node (ref "R12") (pin "2") (pinfunction "2_2") (pintype "passive"))
      (node (ref "U3") (pin "5") (pinfunction "SCL_5") (pintype "input"))
      (node (ref "U4") (pin "36") (pinfunction "IO22_36") (pintype "bidirectional"))
    )
    (net (code "46") (name "SDA") (class "Default")
      (node (ref "R4") (pin "2") (pinfunction "2_2") (pintype "passive"))
      (node (ref "U3") (pin "2") (pinfunction "SDA_2") (pintype "bidirectional"))
      (node (ref "U4") (pin "37") (pinfunction "IO23_37") (pintype "bidirectional"))
    )
    (net (code "47") (name "SLEEP") (class "Default")
      (node (ref "R11") (pin "2") (pinfunction "2_2") (pintype "passive"))
      (node (ref "U1") (pin "17") (pinfunction "NSLEEP_17") (pintype "input"))
      (node (ref "U4") (pin "29") (pinfunction "IO5_29") (pintype "bidirectional"))
    )
    (net (code "48") (name "STEP") (class "Default")
      (node (ref "U1") (pin "22") (pinfunction "STEP_22") (pintype "input"))
      (node (ref "U4") (pin "27") (pinfunction "IO16_27") (pintype "bidirectional"))
    )
    (net (code "49") (name "TXD0") (class "Default")
      (node (ref "U4") (pin "35") (pinfunction "TXD0_35") (pintype "output"))
      (node (ref "U5") (pin "20") (pinfunction "RXD_20") (pintype "input"))
    )
    (net (code "50") (name "VBAT") (class "Default")
      (node (ref "C10") (pin "2") (pinfunction "2_2") (pintype "passive"))
      (node (ref "C11") (pin "2") (pinfunction "2_2") (pintype "passive"))
      (node (ref "C12") (pin "2") (pinfunction "2_2") (pintype "passive"))
      (node (ref "C14") (pin "1") (pinfunction "1_1") (pintype "passive"))
      (node (ref "C15") (pin "1") (pinfunction "1_1") (pintype "passive"))
      (node (ref "C16") (pin "2") (pinfunction "2_2") (pintype "passive"))
      (node (ref "C9") (pin "1") (pinfunction "1_1") (pintype "passive"))
      (node (ref "J1") (pin "2") (pinfunction "2_2") (pintype "passive"))
      (node (ref "R1") (pin "2") (pinfunction "2_2") (pintype "passive"))
      (node (ref "R14") (pin "2") (pinfunction "2_2") (pintype "passive"))
      (node (ref "R25") (pin "2") (pinfunction "2_2") (pintype "passive"))
      (node (ref "U1") (pin "11") (pinfunction "VMB_11") (pintype "power_in"))
      (node (ref "U1") (pin "4") (pinfunction "VMA_4") (pintype "power_in"))
      (node (ref "U6") (pin "3") (pinfunction "VIN_3") (pintype "input"))
    )
    (net (code "51") (name "VBUS") (class "Default")
      (node (ref "C6") (pin "1") (pinfunction "1_1") (pintype "passive"))
      (node (ref "J2") (pin "VBUS") (pinfunction "VBUS_VBUS") (pintype "power_in"))
      (node (ref "R7") (pin "2") (pinfunction "2_2") (pintype "passive"))
      (node (ref "U2") (pin "1") (pinfunction "IN_1") (pintype "power_in"))
      (node (ref "U5") (pin "8") (pinfunction "VBUS_8") (pintype "power_in"))
    )
    (net (code "52") (name "V_REG_OUT") (class "Default")
      (node (ref "C13") (pin "2") (pinfunction "2_2") (pintype "passive"))
      (node (ref "R21") (pin "1") (pinfunction "1_1") (pintype "passive"))
      (node (ref "U1") (pin "15") (pinfunction "V3P3OUT_15") (pintype "output"))
    )
    (net (code "53") (name "unconnected-(J2-PadID)") (class "Default")
      (node (ref "J2") (pin "ID") (pinfunction "ID_ID") (pintype "bidirectional"))
    )
    (net (code "54") (name "unconnected-(SW2-P-PadA)") (class "Default")
      (node (ref "SW2") (pin "A") (pinfunction "P_A") (pintype "passive"))
    )
    (net (code "55") (name "unconnected-(U1-DECAY-Pad19)") (class "Default")
      (node (ref "U1") (pin "19") (pinfunction "DECAY_19") (pintype "input"))
    )
    (net (code "56") (name "unconnected-(U1-NHOME-Pad27)") (class "Default")
      (node (ref "U1") (pin "27") (pinfunction "NHOME_27") (pintype "output"))
    )
    (net (code "57") (name "unconnected-(U2-P4-Pad4)") (class "Default")
      (node (ref "U2") (pin "4") (pinfunction "P4_4") (pintype "bidirectional"))
    )
    (net (code "58") (name "unconnected-(U4-CLK-Pad20)") (class "Default")
      (node (ref "U4") (pin "20") (pinfunction "CLK_20") (pintype "bidirectional"))
    )
    (net (code "59") (name "unconnected-(U4-CMD-Pad19)") (class "Default")
      (node (ref "U4") (pin "19") (pinfunction "CMD_19") (pintype "bidirectional"))
    )
    (net (code "60") (name "unconnected-(U4-I34{slash}A1_6-Pad6)") (class "Default")
      (node (ref "U4") (pin "6") (pinfunction "I34/A1_6_6") (pintype "bidirectional"))
    )
    (net (code "61") (name "unconnected-(U4-IO18-Pad30)") (class "Default")
      (node (ref "U4") (pin "30") (pinfunction "IO18_30") (pintype "bidirectional"))
    )
    (net (code "62") (name "unconnected-(U4-IO19-Pad31)") (class "Default")
      (node (ref "U4") (pin "31") (pinfunction "IO19_31") (pintype "bidirectional"))
    )
    (net (code "63") (name "unconnected-(U4-IO25{slash}DAC1{slash}A2_8-Pad10)") (class "Default")
      (node (ref "U4") (pin "10") (pinfunction "IO25/DAC1/A2_8_10") (pintype "bidirectional"))
    )
    (net (code "64") (name "unconnected-(U4-IO26{slash}DAC2{slash}A2_9-Pad11)") (class "Default")
      (node (ref "U4") (pin "11") (pinfunction "IO26/DAC2/A2_9_11") (pintype "bidirectional"))
    )
    (net (code "65") (name "unconnected-(U4-IO27{slash}A2_7-Pad12)") (class "Default")
      (node (ref "U4") (pin "12") (pinfunction "IO27/A2_7_12") (pintype "bidirectional"))
    )
    (net (code "66") (name "unconnected-(U4-IO32{slash}A1_4{slash}X32P-Pad8)") (class "Default")
      (node (ref "U4") (pin "8") (pinfunction "IO32/A1_4/X32P_8") (pintype "bidirectional"))
    )
    (net (code "67") (name "unconnected-(U4-IO33{slash}A1_5{slash}X32N-Pad9)") (class "Default")
      (node (ref "U4") (pin "9") (pinfunction "IO33/A1_5/X32N_9") (pintype "bidirectional"))
    )
    (net (code "68") (name "unconnected-(U4-IO36{slash}SEN_VP{slash}A1_0-Pad4)") (class "Default")
      (node (ref "U4") (pin "4") (pinfunction "IO36/SEN_VP/A1_0_4") (pintype "passive"))
    )
    (net (code "69") (name "unconnected-(U4-IO39{slash}SEN_VN{slash}A1_3-Pad5)") (class "Default")
      (node (ref "U4") (pin "5") (pinfunction "IO39/SEN_VN/A1_3_5") (pintype "passive"))
    )
    (net (code "70") (name "unconnected-(U4-SD0-Pad21)") (class "Default")
      (node (ref "U4") (pin "21") (pinfunction "SD0_21") (pintype "bidirectional"))
    )
    (net (code "71") (name "unconnected-(U4-SD1-Pad22)") (class "Default")
      (node (ref "U4") (pin "22") (pinfunction "SD1_22") (pintype "bidirectional"))
    )
    (net (code "72") (name "unconnected-(U4-SD2-Pad17)") (class "Default")
      (node (ref "U4") (pin "17") (pinfunction "SD2_17") (pintype "bidirectional"))
    )
    (net (code "73") (name "unconnected-(U4-SD3-Pad18)") (class "Default")
      (node (ref "U4") (pin "18") (pinfunction "SD3_18") (pintype "bidirectional"))
    )
    (net (code "74") (name "unconnected-(U5A-#RST-Pad9)") (class "Default")
      (node (ref "U5") (pin "9") (pinfunction "#RST_9") (pintype "bidirectional"))
    )
    (net (code "75") (name "unconnected-(U5A-#SUSPEND-Pad15)") (class "Default")
      (node (ref "U5") (pin "15") (pinfunction "#SUSPEND_15") (pintype "output"))
    )
    (net (code "76") (name "unconnected-(U5A-CTS-Pad18)") (class "Default")
      (node (ref "U5") (pin "18") (pinfunction "CTS_18") (pintype "input"))
    )
    (net (code "77") (name "unconnected-(U5A-DCD-Pad24)") (class "Default")
      (node (ref "U5") (pin "24") (pinfunction "DCD_24") (pintype "input"))
    )
    (net (code "78") (name "unconnected-(U5A-DSR-Pad22)") (class "Default")
      (node (ref "U5") (pin "22") (pinfunction "DSR_22") (pintype "input"))
    )
    (net (code "79") (name "unconnected-(U5A-GPIO0{slash}TXLED-Pad14)") (class "Default")
      (node (ref "U5") (pin "14") (pinfunction "GPIO0/TXLED_14") (pintype "bidirectional"))
    )
    (net (code "80") (name "unconnected-(U5A-GPIO1{slash}RXLED-Pad13)") (class "Default")
      (node (ref "U5") (pin "13") (pinfunction "GPIO1/RXLED_13") (pintype "bidirectional"))
    )
    (net (code "81") (name "unconnected-(U5A-GPIO2-Pad12)") (class "Default")
      (node (ref "U5") (pin "12") (pinfunction "GPIO2_12") (pintype "bidirectional"))
    )
    (net (code "82") (name "unconnected-(U5A-GPIO3-Pad11)") (class "Default")
      (node (ref "U5") (pin "11") (pinfunction "GPIO3_11") (pintype "bidirectional"))
    )
    (net (code "83") (name "unconnected-(U5A-NC-Pad10)") (class "Default")
      (node (ref "U5") (pin "10") (pinfunction "NC_10") (pintype "no_connect"))
    )
    (net (code "84") (name "unconnected-(U5A-RI-Pad1)") (class "Default")
      (node (ref "U5") (pin "1") (pinfunction "RI_1") (pintype "input"))
    )
    (net (code "85") (name "unconnected-(U5A-SUSPEND-Pad17)") (class "Default")
      (node (ref "U5") (pin "17") (pinfunction "SUSPEND_17") (pintype "output"))
    )
    (net (code "86") (name "unconnected-(U5A-VPP-Pad16)") (class "Default")
      (node (ref "U5") (pin "16") (pinfunction "VPP_16") (pintype "bidirectional"))
    )
  )
)
